# ProtectionChannelA.net
KiCad netlist of a schematic drawn in Altium Designer
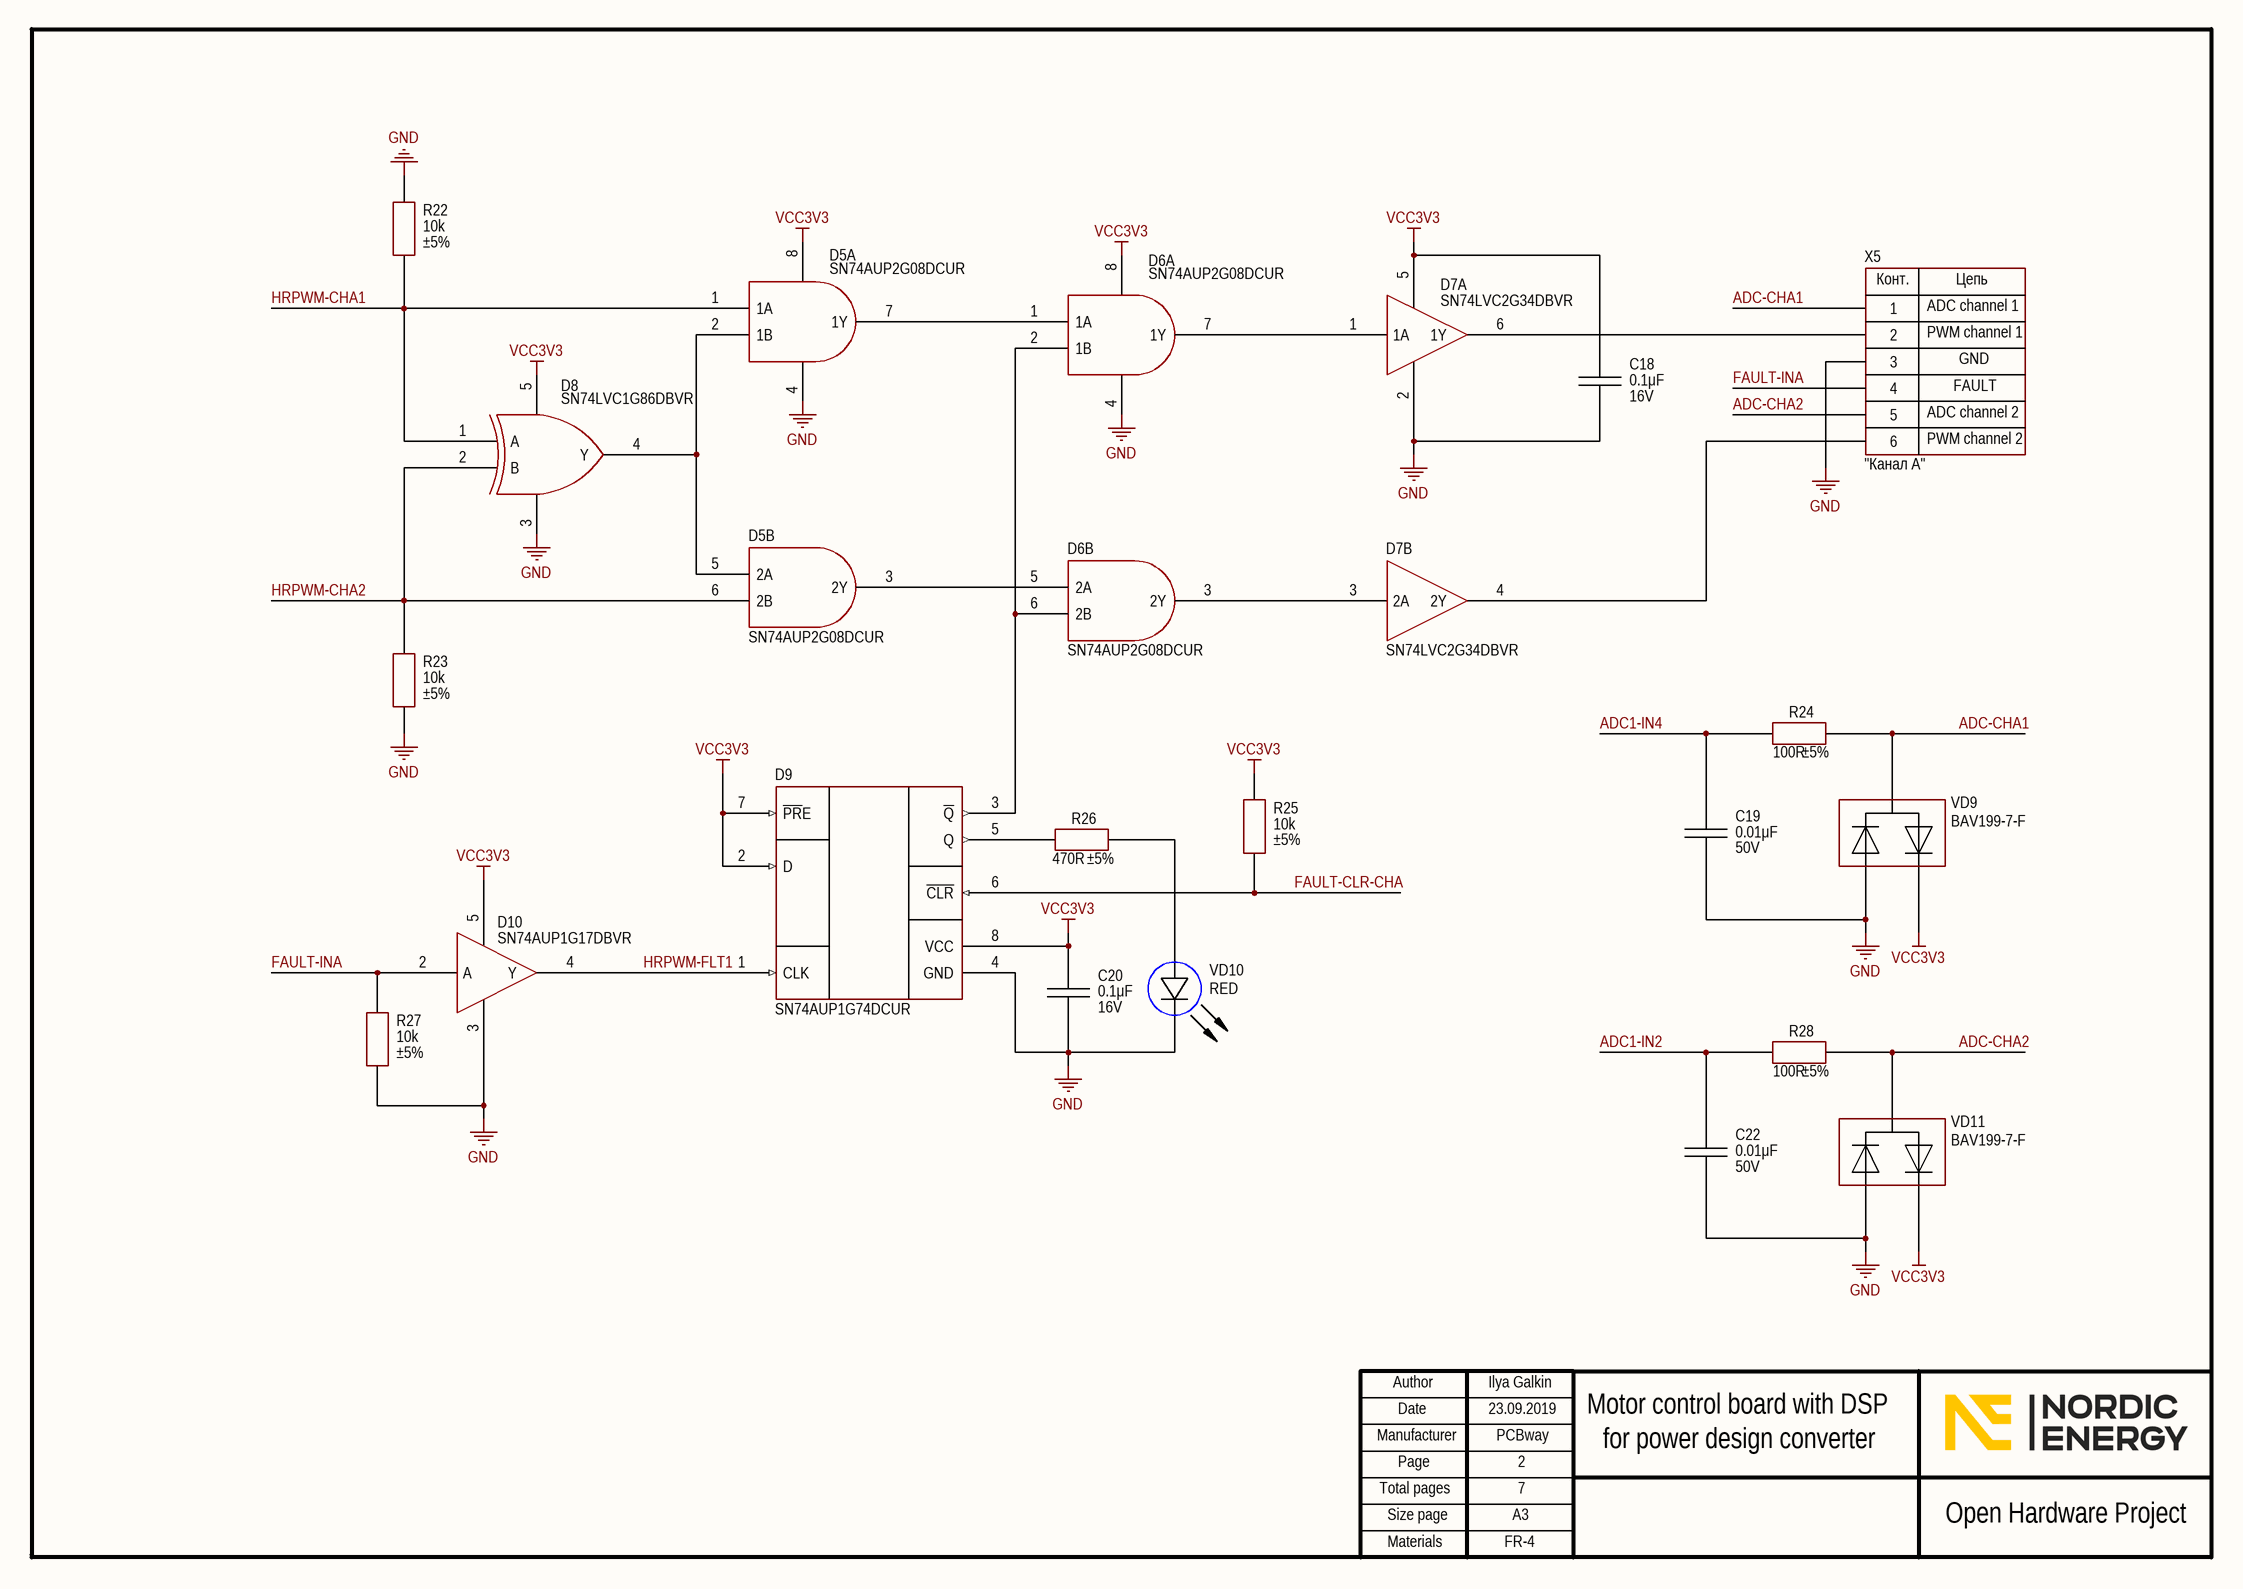
[diagram p0: ProtectionChannelA.SchDoc]

(export (version "E")
  (design (tool "Eeschema 10.0.6"))
  (components
    (comp (ref "C18")
      (value "0.1μF")
      (footprint "CAP: 0805")
      (fields
        (field (name "MANUFACTURER") "Yageo")
        (field (name "PARTNUMBER") "CC0805KRX7R7BB104")
        (field (name "VALUEMANUFACTURERPARTNUMBER") "Ceramic capacitor, 0.1μF, X7R, ±10%, 16V, 0805, -55...+125°C")
        (field (name "VOLTAGE") "16V")
      )
      (libsource (lib "Capacitor") (part "Ceramic_0805"))
    )
    (comp (ref "C19")
      (value "0.01μF")
      (footprint "CAP: 0805")
      (fields
        (field (name "MANUFACTURER") "Yageo")
        (field (name "PARTNUMBER") "CC0805KRX7R9BB103")
        (field (name "VALUEMANUFACTURERPARTNUMBER") "Ceramic capacitor, 0.01μF, X7R, ±10%, 50V, 0805, -55...+125°C")
        (field (name "VOLTAGE") "50V")
      )
      (libsource (lib "Capacitor") (part "Ceramic_0805"))
    )
    (comp (ref "C20")
      (value "0.1μF")
      (footprint "CAP: 0805")
      (fields
        (field (name "MANUFACTURER") "Yageo")
        (field (name "PARTNUMBER") "CC0805KRX7R7BB104")
        (field (name "VALUEMANUFACTURERPARTNUMBER") "Ceramic capacitor, 0.1μF, X7R, ±10%, 16V, 0805, -55...+125°C")
        (field (name "VOLTAGE") "16V")
      )
      (libsource (lib "Capacitor") (part "Ceramic_0805"))
    )
    (comp (ref "C22")
      (value "0.01μF")
      (footprint "CAP: 0805")
      (fields
        (field (name "MANUFACTURER") "Yageo")
        (field (name "PARTNUMBER") "CC0805KRX7R9BB103")
        (field (name "VALUEMANUFACTURERPARTNUMBER") "Ceramic capacitor, 0.01μF, X7R, ±10%, 50V, 0805, -55...+125°C")
        (field (name "VOLTAGE") "50V")
      )
      (libsource (lib "Capacitor") (part "Ceramic_0805"))
    )
    (comp (ref "D5")
      (value "~")
      (footprint "8-VSSOP")
      (description "AND")
      (fields
        (field (name "MANUFACTURER") "Texas Instruments")
        (field (name "VALUEMANUFACTURERPARTNUMBER") "IC logic AND, 0.8...3.6V, -40...+855°C, 8-VSSOP")
        (field (name "PARTNUMBER") "SN74AUP2G08DCUR")
      )
      (libsource (lib "IC. Logic") (part "SN74AUP2G08DCUR"))
    )
    (comp (ref "D6")
      (value "~")
      (footprint "8-VSSOP")
      (description "AND")
      (fields
        (field (name "MANUFACTURER") "Texas Instruments")
        (field (name "VALUEMANUFACTURERPARTNUMBER") "IC logic AND, 0.8...3.6V, -40...+855°C, 8-VSSOP")
        (field (name "PARTNUMBER") "SN74AUP2G08DCUR")
      )
      (libsource (lib "IC. Logic") (part "SN74AUP2G08DCUR"))
    )
    (comp (ref "D7")
      (value "~")
      (footprint "SOT23-6")
      (description "Buffer")
      (fields
        (field (name "MANUFACTURER") "Texas Instruments")
        (field (name "VALUEMANUFACTURERPARTNUMBER") "IC logic buffer, 1.65...5.5V, -40...+125°C, SOT23-6")
        (field (name "PARTNUMBER") "SN74LVC2G34DBVR")
      )
      (libsource (lib "IC. Logic") (part "SN74LVC2G34DBVR"))
    )
    (comp (ref "D8")
      (value "~")
      (footprint "SOT23-5")
      (description "XOR")
      (fields
        (field (name "MANUFACTURER") "Texas Instruments")
        (field (name "VALUEMANUFACTURERPARTNUMBER") "IC logic XOR, 1.65...5.5V, -40...+125°C, SOT23-5")
        (field (name "PARTNUMBER") "SN74LVC1G86DBVR")
      )
      (libsource (lib "IC. Logic") (part "SN74LVC1G86DBVR"))
    )
    (comp (ref "D9")
      (value "~")
      (footprint "8-VSSOP")
      (description "D-trigger")
      (fields
        (field (name "MANUFACTURER") "Texas Instruments")
        (field (name "VALUEMANUFACTURERPARTNUMBER") "ICtrigger D-type, 0.8...3.6V, -40...+85°C, 8-VSSOP")
        (field (name "PARTNUMBER") "SN74AUP1G74DCUR")
      )
      (libsource (lib "IC. Logic") (part "SN74AUP1G74DCUR"))
    )
    (comp (ref "D10")
      (value "~")
      (footprint "SOT23-5")
      (description "Schmitt trigger")
      (fields
        (field (name "MANUFACTURER") "Texas Instruments")
        (field (name "VALUEMANUFACTURERPARTNUMBER") "IC Schmitt trigger, 0.8...3.6V, -40...+85°C, SOT23-6")
        (field (name "PARTNUMBER") "SN74AUP1G17DBVR")
      )
      (libsource (lib "IC. Logic") (part "SN74AUP1G17DBVR"))
    )
    (comp (ref "R22")
      (value "10k")
      (footprint "RES: 0805")
      (fields
        (field (name "MANUFACTURER") "Yageo")
        (field (name "PARTNUMBER") "RC0805JR-0710KL")
        (field (name "VALUEMANUFACTURERPARTNUMBER") "Resistor film, 10k, ±5%, 0805, 0.125W, -55...+125°C")
        (field (name "TOLERANCE") "±5%")
      )
      (libsource (lib "Resistor") (part "Resistor_0805"))
    )
    (comp (ref "R23")
      (value "10k")
      (footprint "RES: 0805")
      (fields
        (field (name "MANUFACTURER") "Yageo")
        (field (name "PARTNUMBER") "RC0805JR-0710KL")
        (field (name "VALUEMANUFACTURERPARTNUMBER") "Resistor film, 10k, ±5%, 0805, 0.125W, -55...+125°C")
        (field (name "TOLERANCE") "±5%")
      )
      (libsource (lib "Resistor") (part "Resistor_0805"))
    )
    (comp (ref "R24")
      (value "100R")
      (footprint "RES: 0805")
      (fields
        (field (name "MANUFACTURER") "Yageo")
        (field (name "PARTNUMBER") "RC0805JR-07100RL")
        (field (name "VALUEMANUFACTURERPARTNUMBER") "Resistor film, 100R, ±5%, 0805, 0.125W, -55...+125°C")
        (field (name "TOLERANCE") "±5%")
      )
      (libsource (lib "") (part "Resistor_0805_1"))
    )
    (comp (ref "R25")
      (value "10k")
      (footprint "RES: 0805")
      (fields
        (field (name "MANUFACTURER") "Yageo")
        (field (name "PARTNUMBER") "RC0805JR-0710KL")
        (field (name "VALUEMANUFACTURERPARTNUMBER") "Resistor film, 10k, ±5%, 0805, 0.125W, -55...+125°C")
        (field (name "TOLERANCE") "±5%")
      )
      (libsource (lib "Resistor") (part "Resistor_0805"))
    )
    (comp (ref "R26")
      (value "470R")
      (footprint "RES: 0805")
      (fields
        (field (name "MANUFACTURER") "Yageo")
        (field (name "PARTNUMBER") "RC0805JR-07470RL")
        (field (name "VALUEMANUFACTURERPARTNUMBER") "Resistor film, 470R, ±5%, 0805, 0.125W, -55...+125°C")
        (field (name "TOLERANCE") "±5%")
      )
      (libsource (lib "") (part "Resistor_0805_2"))
    )
    (comp (ref "R27")
      (value "10k")
      (footprint "RES: 0805")
      (fields
        (field (name "MANUFACTURER") "Yageo")
        (field (name "PARTNUMBER") "RC0805JR-0710KL")
        (field (name "VALUEMANUFACTURERPARTNUMBER") "Resistor film, 10k, ±5%, 0805, 0.125W, -55...+125°C")
        (field (name "TOLERANCE") "±5%")
      )
      (libsource (lib "Resistor") (part "Resistor_0805"))
    )
    (comp (ref "R28")
      (value "100R")
      (footprint "RES: 0805")
      (fields
        (field (name "MANUFACTURER") "Yageo")
        (field (name "PARTNUMBER") "RC0805JR-07100RL")
        (field (name "VALUEMANUFACTURERPARTNUMBER") "Resistor film, 100R, ±5%, 0805, 0.125W, -55...+125°C")
        (field (name "TOLERANCE") "±5%")
      )
      (libsource (lib "") (part "Resistor_0805_1"))
    )
    (comp (ref "VD9")
      (value "~")
      (footprint "SOT23")
      (fields
        (field (name "MANUFACTURER") "Diodes Incorporated")
        (field (name "VALUEMANUFACTURERPARTNUMBER") "Diode array, 85V, 140mA, 1.1V, 3us, SOT-23, -65...+150°C")
        (field (name "VOLTAGE") "85V")
        (field (name "PARTNUMBER") "BAV199-7-F")
      )
      (libsource (lib "Diode") (part "Diode_array"))
    )
    (comp (ref "VD10")
      (value "~")
      (footprint "LED: 0805R")
      (fields
        (field (name "MANUFACTURER") "Wurth")
        (field (name "VALUEMANUFACTURERPARTNUMBER") "LED, 20mA, 2V, 0805, -55...+150°C")
        (field (name "PARTNUMBER") "150080RS75000")
        (field (name "COLOR") "RED")
      )
      (libsource (lib "Diode") (part "LED_single"))
    )
    (comp (ref "VD11")
      (value "~")
      (footprint "SOT23")
      (fields
        (field (name "MANUFACTURER") "Diodes Incorporated")
        (field (name "VALUEMANUFACTURERPARTNUMBER") "Diode array, 85V, 140mA, 1.1V, 3us, SOT-23, -65...+150°C")
        (field (name "VOLTAGE") "85V")
        (field (name "PARTNUMBER") "BAV199-7-F")
      )
      (libsource (lib "Diode") (part "Diode_array"))
    )
    (comp (ref "X5")
      (value "~")
      (footprint "CON: PLD-6")
      (fields
        (field (name "MANUFACTURER") "Connfly")
        (field (name "VALUEMANUFACTURERPARTNUMBER") "Connector, 6pin, 2.54mm, 500VAC, 3A")
        (field (name "PARTNUMBER") "PLD-6")
        (field (name "COMMENTTEXT") "\"Канал А\"")
      )
      (libsource (lib "Connector") (part "PLD-6"))
    )
  )
  (nets
    (net (code "1") (name "/ADC-CHA1") (class "Default")
      (node (ref "R24") (pin "2") (pinfunction "2_2") (pintype "passive"))
      (node (ref "VD9") (pin "3") (pinfunction "3_3") (pintype "passive"))
      (node (ref "X5") (pin "1") (pinfunction "1_1") (pintype "passive"))
    )
    (net (code "2") (name "/ADC-CHA2") (class "Default")
      (node (ref "R28") (pin "2") (pinfunction "2_2") (pintype "passive"))
      (node (ref "VD11") (pin "3") (pinfunction "3_3") (pintype "passive"))
      (node (ref "X5") (pin "5") (pinfunction "5_5") (pintype "power_in"))
    )
    (net (code "3") (name "/ADC1-IN2") (class "Default")
      (node (ref "C22") (pin "2") (pinfunction "2_2") (pintype "power_in"))
      (node (ref "R28") (pin "1") (pinfunction "1_1") (pintype "passive"))
    )
    (net (code "4") (name "/ADC1-IN4") (class "Default")
      (node (ref "C19") (pin "2") (pinfunction "2_2") (pintype "power_in"))
      (node (ref "R24") (pin "1") (pinfunction "1_1") (pintype "passive"))
    )
    (net (code "5") (name "/FAULT-CLR-CHA") (class "Default")
      (node (ref "D9") (pin "6") (pinfunction "~{CLR}_6") (pintype "input"))
      (node (ref "R25") (pin "2") (pinfunction "2_2") (pintype "passive"))
    )
    (net (code "6") (name "/FAULT-INA") (class "Default")
      (node (ref "D10") (pin "2") (pinfunction "A_2") (pintype "passive"))
      (node (ref "R27") (pin "1") (pinfunction "1_1") (pintype "passive"))
      (node (ref "X5") (pin "4") (pinfunction "4_4") (pintype "power_in"))
    )
    (net (code "7") (name "/HRPWM-CHA1") (class "Default")
      (node (ref "D5") (pin "1") (pinfunction "1A_1") (pintype "passive"))
      (node (ref "D8") (pin "1") (pinfunction "A_1") (pintype "passive"))
      (node (ref "R22") (pin "2") (pinfunction "2_2") (pintype "passive"))
    )
    (net (code "8") (name "/HRPWM-CHA2") (class "Default")
      (node (ref "D5") (pin "6") (pinfunction "2B_6") (pintype "passive"))
      (node (ref "D8") (pin "2") (pinfunction "B_2") (pintype "passive"))
      (node (ref "R23") (pin "1") (pinfunction "1_1") (pintype "passive"))
    )
    (net (code "9") (name "/HRPWM-FLT1") (class "Default")
      (node (ref "D10") (pin "4") (pinfunction "Y_4") (pintype "passive"))
      (node (ref "D9") (pin "1") (pinfunction "CLK_1") (pintype "input"))
    )
    (net (code "10") (name "GND") (class "Default")
      (node (ref "C18") (pin "1") (pinfunction "1_1") (pintype "power_in"))
      (node (ref "C19") (pin "1") (pinfunction "1_1") (pintype "power_in"))
      (node (ref "C20") (pin "1") (pinfunction "1_1") (pintype "power_in"))
      (node (ref "C22") (pin "1") (pinfunction "1_1") (pintype "power_in"))
      (node (ref "D10") (pin "3") (pintype "passive"))
      (node (ref "D5") (pin "4") (pintype "passive"))
      (node (ref "D6") (pin "4") (pintype "passive"))
      (node (ref "D7") (pin "2") (pintype "passive"))
      (node (ref "D8") (pin "3") (pintype "passive"))
      (node (ref "D9") (pin "4") (pinfunction "GND_4") (pintype "passive"))
      (node (ref "R22") (pin "1") (pinfunction "1_1") (pintype "passive"))
      (node (ref "R23") (pin "2") (pinfunction "2_2") (pintype "passive"))
      (node (ref "R27") (pin "2") (pinfunction "2_2") (pintype "passive"))
      (node (ref "VD10") (pin "2") (pinfunction "C_2") (pintype "passive"))
      (node (ref "VD11") (pin "1") (pinfunction "1_1") (pintype "passive"))
      (node (ref "VD9") (pin "1") (pinfunction "1_1") (pintype "passive"))
      (node (ref "X5") (pin "3") (pinfunction "3_3") (pintype "power_in"))
    )
    (net (code "11") (name "Net-(D5A-1B)") (class "Default")
      (node (ref "D5") (pin "2") (pinfunction "1B_2") (pintype "passive"))
      (node (ref "D5") (pin "5") (pinfunction "2A_5") (pintype "passive"))
      (node (ref "D8") (pin "4") (pinfunction "Y_4") (pintype "passive"))
    )
    (net (code "12") (name "Net-(D5A-1Y)") (class "Default")
      (node (ref "D5") (pin "7") (pinfunction "1Y_7") (pintype "passive"))
      (node (ref "D6") (pin "1") (pinfunction "1A_1") (pintype "passive"))
    )
    (net (code "13") (name "Net-(D5B-2Y)") (class "Default")
      (node (ref "D5") (pin "3") (pinfunction "2Y_3") (pintype "passive"))
      (node (ref "D6") (pin "5") (pinfunction "2A_5") (pintype "passive"))
    )
    (net (code "14") (name "Net-(D6A-1B)") (class "Default")
      (node (ref "D6") (pin "2") (pinfunction "1B_2") (pintype "passive"))
      (node (ref "D6") (pin "6") (pinfunction "2B_6") (pintype "passive"))
      (node (ref "D9") (pin "3") (pinfunction "~{Q}_3") (pintype "output"))
    )
    (net (code "15") (name "Net-(D6A-1Y)") (class "Default")
      (node (ref "D6") (pin "7") (pinfunction "1Y_7") (pintype "passive"))
      (node (ref "D7") (pin "1") (pinfunction "1A_1") (pintype "passive"))
    )
    (net (code "16") (name "Net-(D6B-2Y)") (class "Default")
      (node (ref "D6") (pin "3") (pinfunction "2Y_3") (pintype "passive"))
      (node (ref "D7") (pin "3") (pinfunction "2A_3") (pintype "passive"))
    )
    (net (code "17") (name "Net-(D7A-1Y)") (class "Default")
      (node (ref "D7") (pin "6") (pinfunction "1Y_6") (pintype "passive"))
      (node (ref "X5") (pin "2") (pinfunction "2_2") (pintype "passive"))
    )
    (net (code "18") (name "Net-(D7B-2Y)") (class "Default")
      (node (ref "D7") (pin "4") (pinfunction "2Y_4") (pintype "passive"))
      (node (ref "X5") (pin "6") (pinfunction "6_6") (pintype "power_in"))
    )
    (net (code "19") (name "Net-(D9-Q)") (class "Default")
      (node (ref "D9") (pin "5") (pinfunction "Q_5") (pintype "output"))
      (node (ref "R26") (pin "2") (pinfunction "2_2") (pintype "passive"))
    )
    (net (code "20") (name "Net-(VD10-A)") (class "Default")
      (node (ref "R26") (pin "1") (pinfunction "1_1") (pintype "passive"))
      (node (ref "VD10") (pin "1") (pinfunction "A_1") (pintype "passive"))
    )
    (net (code "21") (name "VCC3V3") (class "Default")
      (node (ref "C18") (pin "2") (pinfunction "2_2") (pintype "power_in"))
      (node (ref "C20") (pin "2") (pinfunction "2_2") (pintype "power_in"))
      (node (ref "D10") (pin "5") (pintype "passive"))
      (node (ref "D5") (pin "8") (pintype "passive"))
      (node (ref "D6") (pin "8") (pintype "passive"))
      (node (ref "D7") (pin "5") (pintype "passive"))
      (node (ref "D8") (pin "5") (pintype "passive"))
      (node (ref "D9") (pin "2") (pinfunction "D_2") (pintype "input"))
      (node (ref "D9") (pin "7") (pinfunction "~{PR}E_7") (pintype "input"))
      (node (ref "D9") (pin "8") (pinfunction "VCC_8") (pintype "passive"))
      (node (ref "R25") (pin "1") (pinfunction "1_1") (pintype "passive"))
      (node (ref "VD11") (pin "2") (pinfunction "2_2") (pintype "passive"))
      (node (ref "VD9") (pin "2") (pinfunction "2_2") (pintype "passive"))
    )
  )
)
